# GSM-Arduino-Custom-Board.net
KiCad netlist of a schematic drawn in Altium Designer
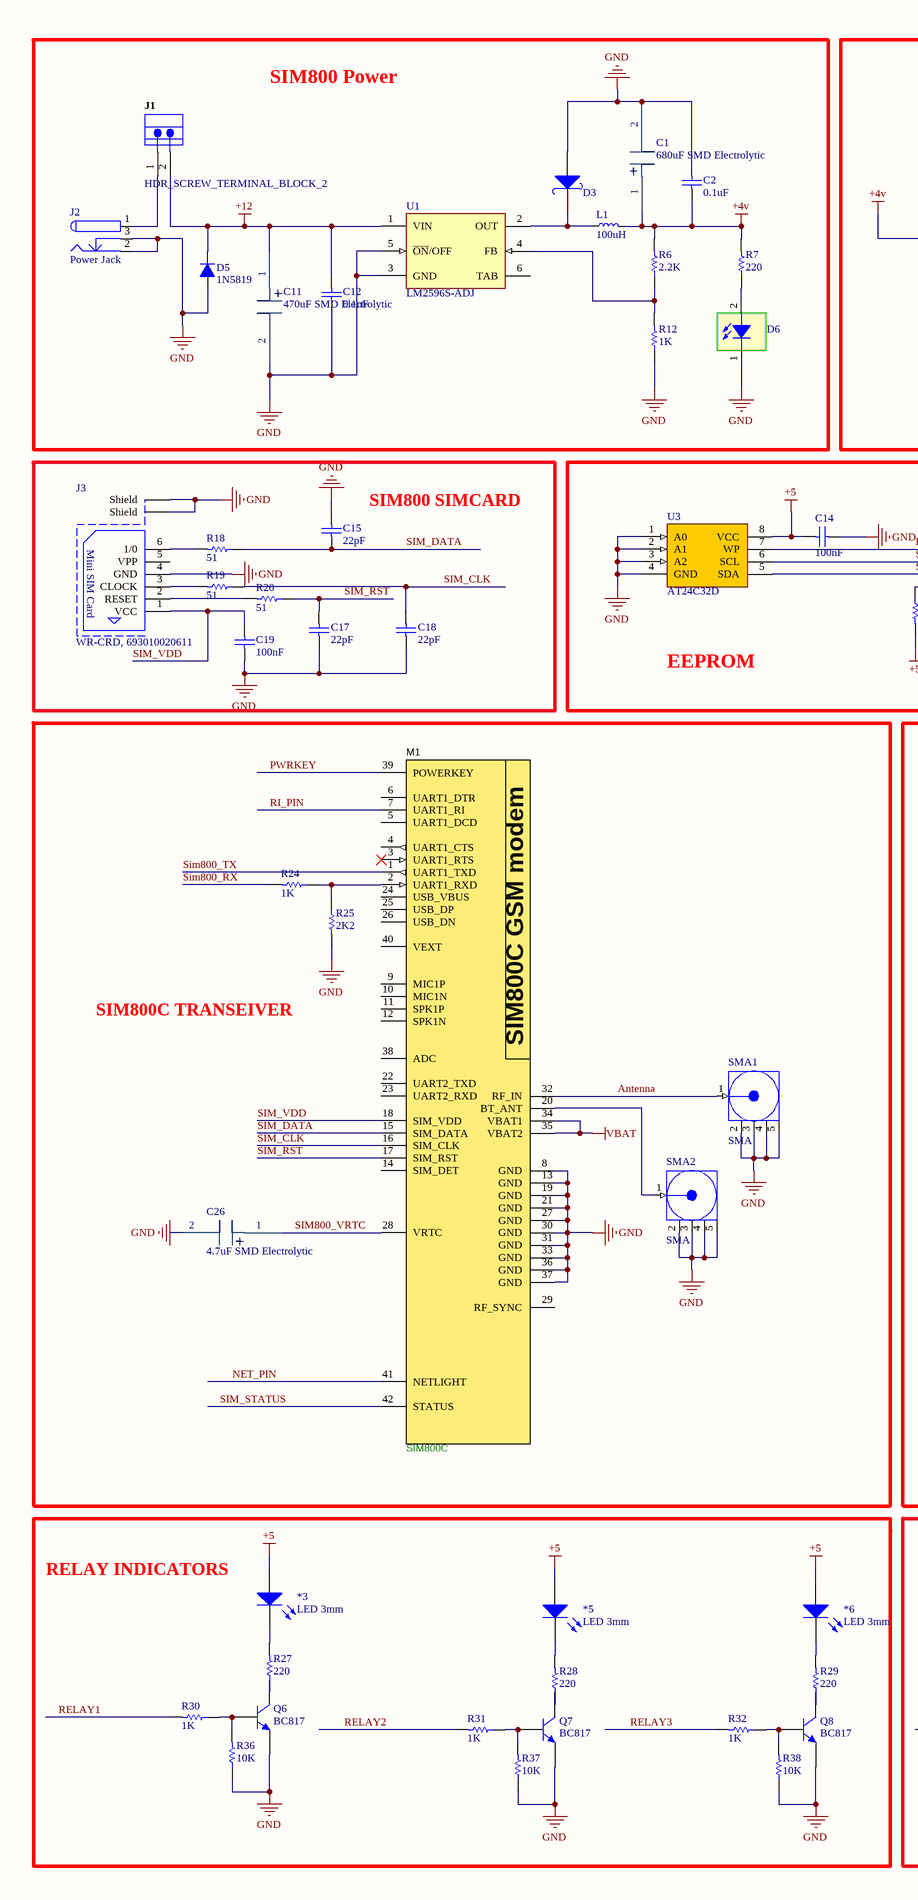
[diagram p0: GSM-Arduino-Custom-Board.SchDoc, left]
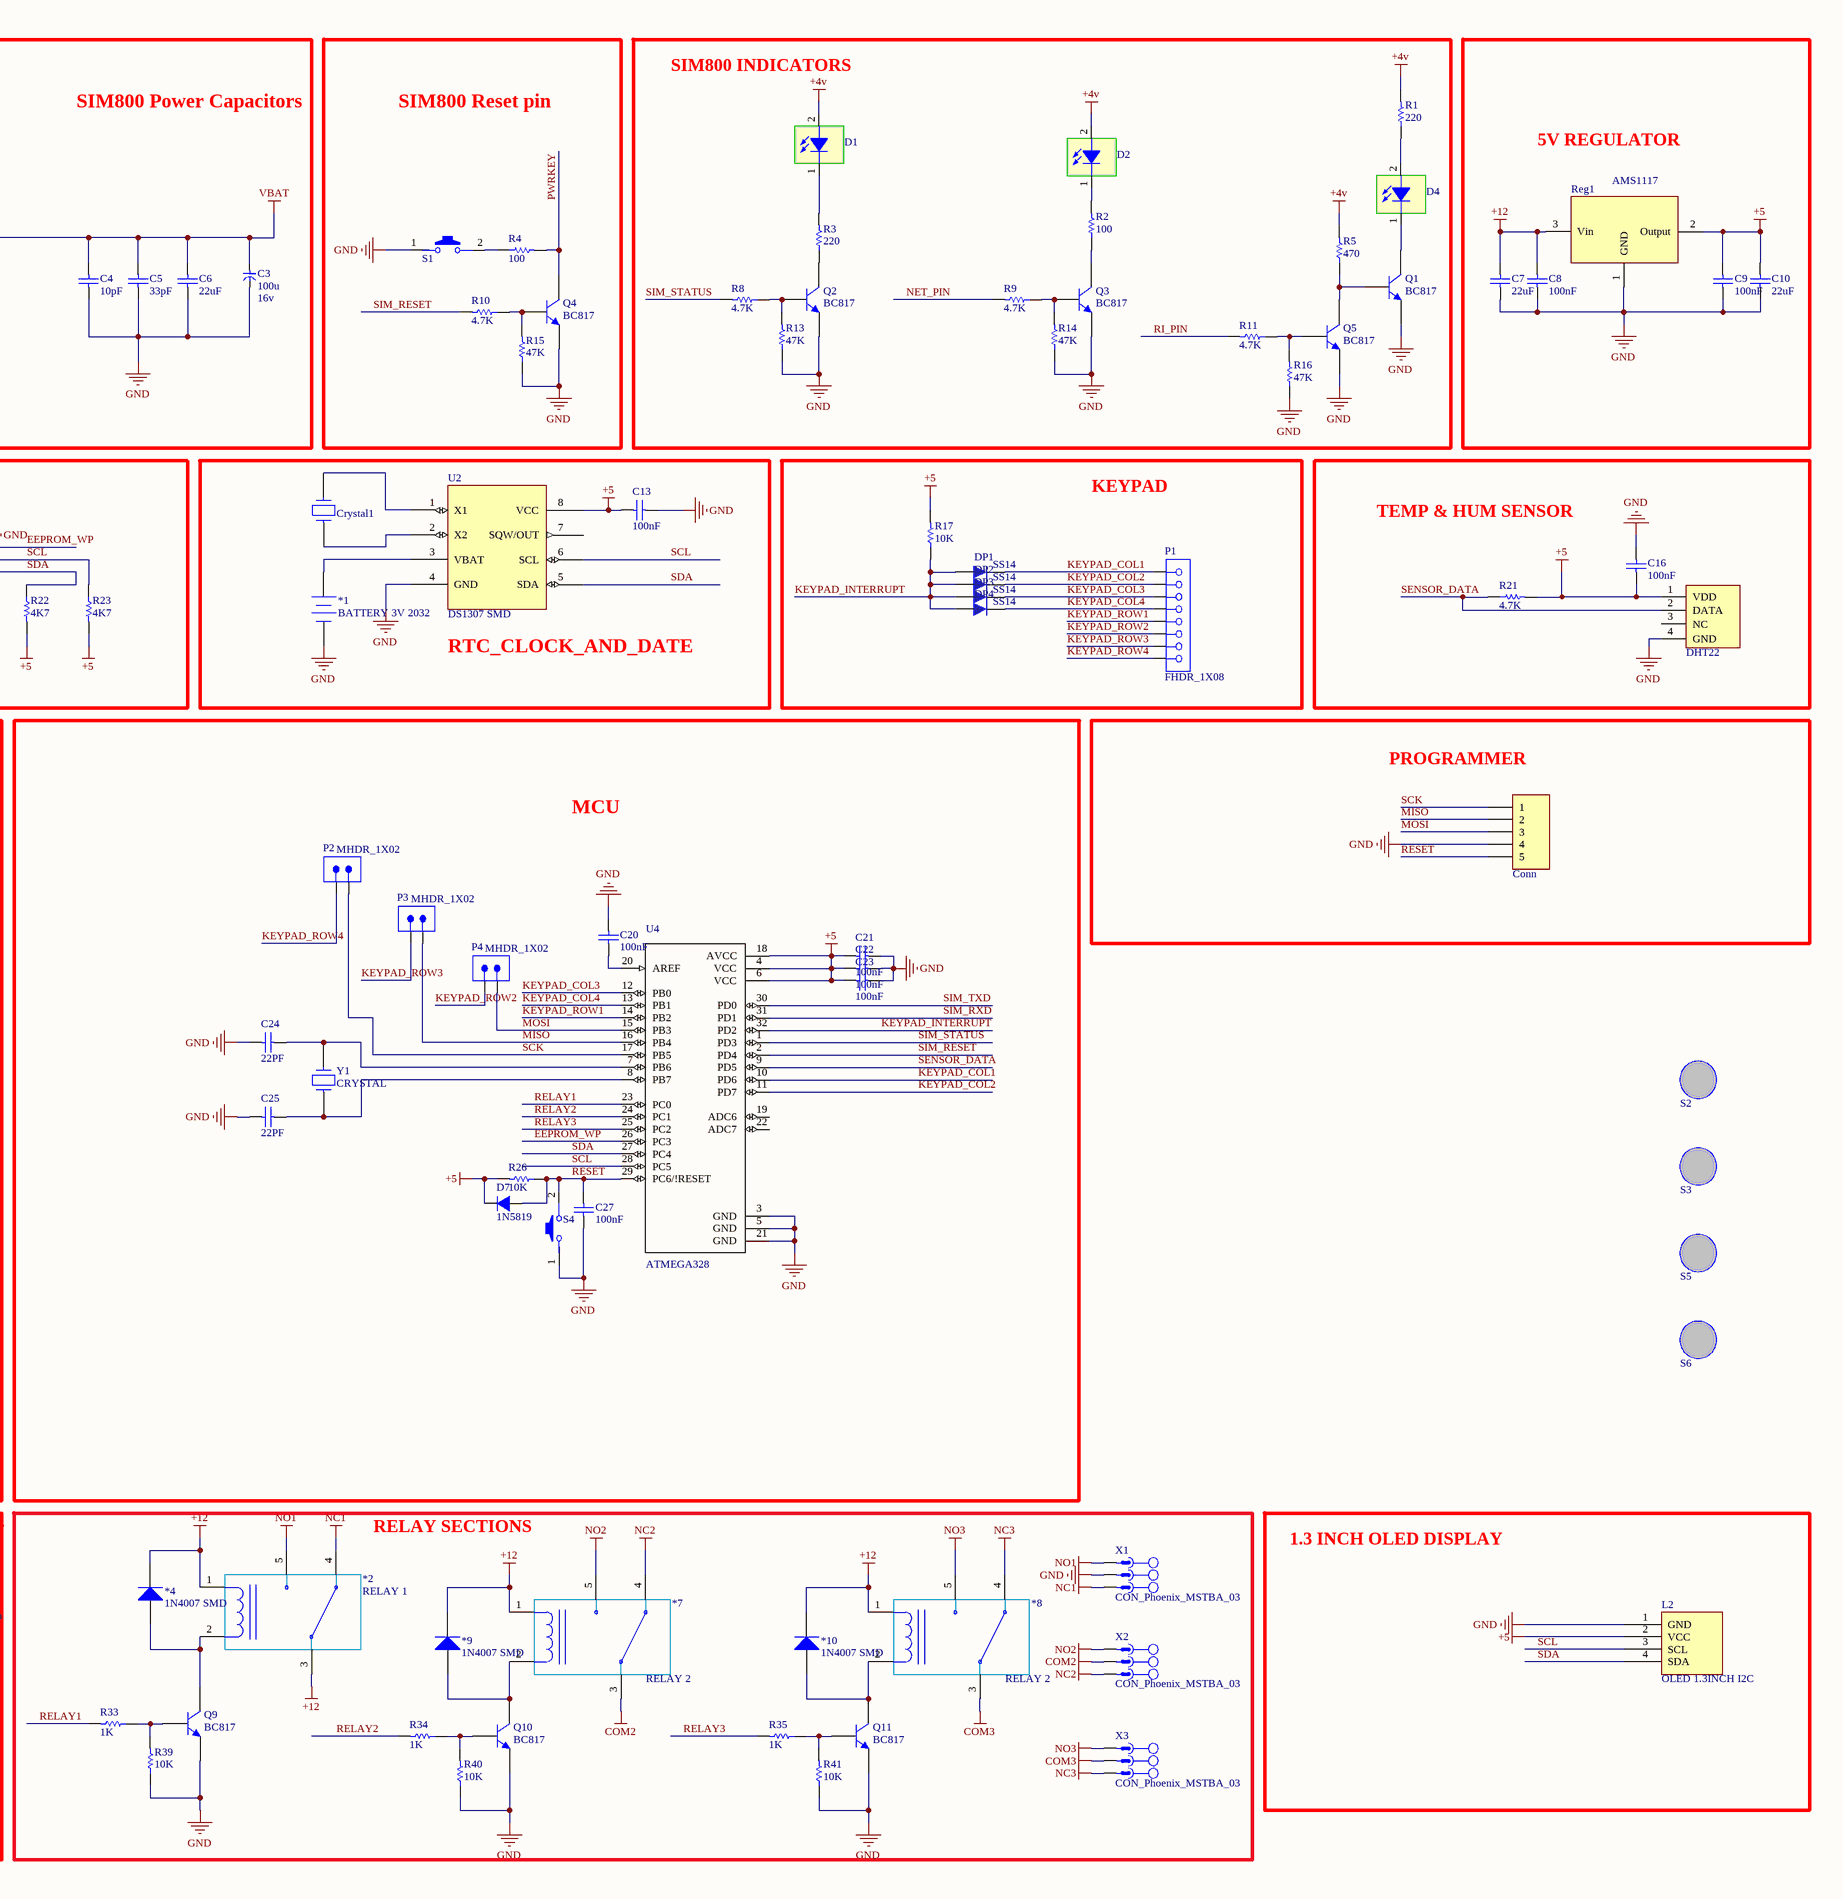
[diagram p1: GSM-Arduino-Custom-Board.SchDoc, right]

(export (version "E")
  (design (tool "Eeschema 10.0.6"))
  (components
    (comp (ref "*1")
      (value "BATTERY 3V 2032")
      (footprint "batt")
      (libsource (lib "General_04") (part "BATTERY 3V 2032"))
    )
    (comp (ref "*2") (value "RELAY 1") (footprint "relay 3") (libsource (lib "General_04") (part "RELAY 1")))
    (comp (ref "*3") (value "LED 3mm") (footprint "led 3mm") (libsource (lib "General_04") (part "LED 3mm")))
    (comp (ref "*4")
      (value "1N4007 SMD")
      (footprint "1N4007 SMD")
      (libsource (lib "General_04") (part "1N4007 SMD"))
    )
    (comp (ref "*5") (value "LED 3mm") (footprint "led 3mm") (libsource (lib "General_04") (part "LED 3mm")))
    (comp (ref "*6") (value "LED 3mm") (footprint "led 3mm") (libsource (lib "General_04") (part "LED 3mm")))
    (comp (ref "*7") (value "RELAY 2") (footprint "relay 3") (libsource (lib "General_04") (part "RELAY 1")))
    (comp (ref "*8") (value "RELAY 2") (footprint "relay 3") (libsource (lib "General_04") (part "RELAY 1")))
    (comp (ref "*9")
      (value "1N4007 SMD")
      (footprint "1N4007 SMD")
      (libsource (lib "General_04") (part "1N4007 SMD"))
    )
    (comp (ref "*10")
      (value "1N4007 SMD")
      (footprint "1N4007 SMD")
      (libsource (lib "General_04") (part "1N4007 SMD"))
    )
    (comp (ref "C1")
      (value "680uF SMD Electrolytic")
      (footprint "SMD Electrolytic Capacitor 8 x 10.2")
      (libsource (lib "RezaKH-Exclusive-LIB") (part "SMD Electrolytic Capacitor 8 x 10.2"))
    )
    (comp (ref "C2")
      (value "0.1uF")
      (footprint "CAPC4817X12N")
      (description "CAP 1206")
      (fields (field (name "DESIGNER") "Abbas Basereh"))
      (libsource (lib "General 1") (part "CAP SMD 1206"))
    )
    (comp (ref "C3")
      (value "100u")
      (footprint "TANTAL CAPACITOR SMD B")
      (description "TANTAL CAPACITOR")
      (fields (field (name "POWER") "16v") (field (name "DESIGNER") "Danial mirzaei"))
      (libsource (lib "My_Lib") (part "TANTAL CAP SMD B"))
    )
    (comp (ref "C4")
      (value "10pF")
      (footprint "CAPC4817X12N")
      (description "CAP 1206")
      (fields (field (name "DESIGNER") "Abbas Basereh"))
      (libsource (lib "General 1") (part "CAP SMD 1206"))
    )
    (comp (ref "C5")
      (value "33pF")
      (footprint "CAPC4817X12N")
      (description "CAP 1206")
      (fields (field (name "DESIGNER") "Abbas Basereh"))
      (libsource (lib "General 1") (part "CAP SMD 1206"))
    )
    (comp (ref "C6")
      (value "22uF")
      (footprint "CAPC4817X12N")
      (description "CAP 1206")
      (fields (field (name "DESIGNER") "Abbas Basereh"))
      (libsource (lib "General 1") (part "CAP SMD 1206"))
    )
    (comp (ref "C7")
      (value "22uF")
      (footprint "CAPC4817X12N")
      (description "CAP 1206")
      (fields (field (name "DESIGNER") "Abbas Basereh"))
      (libsource (lib "General 1") (part "CAP SMD 1206"))
    )
    (comp (ref "C8")
      (value "100nF")
      (footprint "CAPC4817X12N")
      (description "CAP 1206")
      (fields (field (name "DESIGNER") "Abbas Basereh"))
      (libsource (lib "General 1") (part "CAP SMD 1206"))
    )
    (comp (ref "C9")
      (value "100nF")
      (footprint "CAPC4817X12N")
      (description "CAP 1206")
      (fields (field (name "DESIGNER") "Abbas Basereh"))
      (libsource (lib "General 1") (part "CAP SMD 1206"))
    )
    (comp (ref "C10")
      (value "22uF")
      (footprint "CAPC4817X12N")
      (description "CAP 1206")
      (fields (field (name "DESIGNER") "Abbas Basereh"))
      (libsource (lib "General 1") (part "CAP SMD 1206"))
    )
    (comp (ref "C11")
      (value "470uF SMD Electrolytic")
      (footprint "SMD Electrolytic Capacitor 8 x 10.2")
      (libsource (lib "RezaKH-Exclusive-LIB") (part "SMD Electrolytic Capacitor 8 x 10.2"))
    )
    (comp (ref "C12")
      (value "0.1uF")
      (footprint "CAPC4817X12N")
      (description "CAP 1206")
      (fields (field (name "DESIGNER") "Abbas Basereh"))
      (libsource (lib "General 1") (part "CAP SMD 1206"))
    )
    (comp (ref "C13")
      (value "100nF")
      (footprint "CAPC4817X12N")
      (description "CAP 1206")
      (fields (field (name "DESIGNER") "Abbas Basereh"))
      (libsource (lib "General 1") (part "CAP SMD 1206"))
    )
    (comp (ref "C14")
      (value "100nF")
      (footprint "CAPC4817X12N")
      (description "CAP 1206")
      (fields (field (name "DESIGNER") "Abbas Basereh"))
      (libsource (lib "General 1") (part "CAP SMD 1206"))
    )
    (comp (ref "C15")
      (value "22pF")
      (footprint "CAPC4817X12N")
      (description "CAP 1206")
      (fields (field (name "DESIGNER") "Abbas Basereh"))
      (libsource (lib "General 1") (part "CAP SMD 1206"))
    )
    (comp (ref "C16")
      (value "100nF")
      (footprint "CAPC4817X12N")
      (description "CAP 1206")
      (fields (field (name "DESIGNER") "Abbas Basereh"))
      (libsource (lib "General 1") (part "CAP SMD 1206"))
    )
    (comp (ref "C17")
      (value "22pF")
      (footprint "CAPC4817X12N")
      (description "CAP 1206")
      (fields (field (name "DESIGNER") "Abbas Basereh"))
      (libsource (lib "General 1") (part "CAP SMD 1206"))
    )
    (comp (ref "C18")
      (value "22pF")
      (footprint "CAPC4817X12N")
      (description "CAP 1206")
      (fields (field (name "DESIGNER") "Abbas Basereh"))
      (libsource (lib "General 1") (part "CAP SMD 1206"))
    )
    (comp (ref "C19")
      (value "100nF")
      (footprint "CAPC4817X12N")
      (description "CAP 1206")
      (fields (field (name "DESIGNER") "Abbas Basereh"))
      (libsource (lib "General 1") (part "CAP SMD 1206"))
    )
    (comp (ref "C20")
      (value "100nF")
      (footprint "CAPC4817X12N")
      (description "CAP 1206")
      (fields (field (name "DESIGNER") "Abbas Basereh"))
      (libsource (lib "General 1") (part "CAP SMD 1206"))
    )
    (comp (ref "C21")
      (value "100nF")
      (footprint "CAPC4817X12N")
      (description "CAP 1206")
      (fields (field (name "DESIGNER") "Abbas Basereh"))
      (libsource (lib "General 1") (part "CAP SMD 1206"))
    )
    (comp (ref "C22")
      (value "100nF")
      (footprint "CAPC4817X12N")
      (description "CAP 1206")
      (fields (field (name "DESIGNER") "Abbas Basereh"))
      (libsource (lib "General 1") (part "CAP SMD 1206"))
    )
    (comp (ref "C23")
      (value "100nF")
      (footprint "CAPC4817X12N")
      (description "CAP 1206")
      (fields (field (name "DESIGNER") "Abbas Basereh"))
      (libsource (lib "General 1") (part "CAP SMD 1206"))
    )
    (comp (ref "C24")
      (value "22PF")
      (footprint "CAPC4817X12N")
      (description "CAP 1206")
      (fields (field (name "DESIGNER") "Abbas Basereh"))
      (libsource (lib "General 1") (part "CAP SMD 1206"))
    )
    (comp (ref "C25")
      (value "22PF")
      (footprint "CAPC4817X12N")
      (description "CAP 1206")
      (fields (field (name "DESIGNER") "Abbas Basereh"))
      (libsource (lib "General 1") (part "CAP SMD 1206"))
    )
    (comp (ref "C26")
      (value "4.7uF SMD Electrolytic")
      (footprint "SMD Electrolytic Capacitor 4x5.2")
      (libsource (lib "RezaKH-Exclusive-LIB") (part "SMD Electrolytic Capacitor 8 x 10.2"))
    )
    (comp (ref "C27")
      (value "100nF")
      (footprint "CAPC4817X12N")
      (description "CAP 1206")
      (fields (field (name "DESIGNER") "Abbas Basereh"))
      (libsource (lib "General 1") (part "CAP SMD 1206"))
    )
    (comp (ref "Conn")
      (value "Telecommunications")
      (footprint "Teleconn_5pin")
      (fields (field (name "PUBLISHER") "Altium Limited"))
      (libsource (lib "General_10") (part "CON_Telecommunications_5pin"))
    )
    (comp (ref "Crystal1")
      (value "Crystal")
      (footprint "Crystal_2")
      (fields (field (name "PUBLISHER") "Altium Limited"))
      (libsource (lib "General_10") (part "Crystal.."))
    )
    (comp (ref "D1")
      (value "SMD 1206 LED")
      (footprint "LED 1206")
      (libsource (lib "General_14") (part "LED SMD 1206"))
    )
    (comp (ref "D2")
      (value "SMD 1206 LED")
      (footprint "LED 1206")
      (libsource (lib "General_14") (part "LED SMD 1206"))
    )
    (comp (ref "D3")
      (value "1n5822")
      (footprint "DO-214AB(SMC)")
      (description "Schottky Rectifiers")
      (fields
        (field (name "MANUFACTURER") "ON Semiconductor/Fairchild")
        (field (name "DESIGNER") "Abbas Basereh")
      )
      (libsource (lib "General_14") (part "1N5822 SMD"))
    )
    (comp (ref "D4")
      (value "SMD 1206 LED")
      (footprint "LED 1206")
      (libsource (lib "General_14") (part "LED SMD 1206"))
    )
    (comp (ref "D5")
      (value "1N5819")
      (footprint "DO-214AC")
      (description "Schottky diode")
      (libsource (lib "General_09") (part "1N5819"))
    )
    (comp (ref "D6")
      (value "SMD 1206 LED")
      (footprint "LED 1206")
      (libsource (lib "General_14") (part "LED SMD 1206"))
    )
    (comp (ref "D7")
      (value "1N5819")
      (footprint "DO-214AC")
      (description "Schottky diode")
      (libsource (lib "General_09") (part "1N5819"))
    )
    (comp (ref "DHT22")
      (value "DHT22")
      (footprint "DHT22")
      (description "Temprature & Humidity Sensor")
      (libsource (lib "General_12") (part "DHT22"))
    )
    (comp (ref "DP1")
      (value "SS14")
      (footprint "430X270D")
      (description "Schottkey Rectifiers")
      (fields (field (name "DESIGNER") "Abbas Basereh"))
      (libsource (lib "General 1") (part "1N5819"))
    )
    (comp (ref "DP2")
      (value "SS14")
      (footprint "430X270D")
      (description "Schottkey Rectifiers")
      (fields (field (name "DESIGNER") "Abbas Basereh"))
      (libsource (lib "General 1") (part "1N5819"))
    )
    (comp (ref "DP3")
      (value "SS14")
      (footprint "430X270D")
      (description "Schottkey Rectifiers")
      (fields (field (name "DESIGNER") "Abbas Basereh"))
      (libsource (lib "General 1") (part "1N5819"))
    )
    (comp (ref "DP4")
      (value "SS14")
      (footprint "430X270D")
      (description "Schottkey Rectifiers")
      (fields (field (name "DESIGNER") "Abbas Basereh"))
      (libsource (lib "General 1") (part "1N5819"))
    )
    (comp (ref "J1")
      (value "HDR_SCREW_TERMINAL_BLOCK_2")
      (footprint "Socket Blue 2")
      (fields (field (name "DESIGNER") "Eng. Saeid Jorablo") (field (name "PUBLISHER") "SJ UnLimited"))
      (libsource (lib "Sockets And Connectors") (part "HDR_SCREW_TERMINAL_BLOCK_2"))
    )
    (comp (ref "J2")
      (value "Power Jack")
      (footprint "Power Jack")
      (fields (field (name "DESIGNER") "Saeid Jorablo"))
      (libsource (lib "RezaKH-Exclusive-LIB") (part "Power Jack"))
    )
    (comp (ref "J3")
      (value "WR-CRD, 693010020611")
      (footprint "693010020611")
      (description "WR-CRD Mini SIM")
      (fields
        (field (name "MANUFACTURER") "Würth Elektronik eiSos GmbH")
        (field (name "PARTNO") "693010020611")
        (field (name "CREATED BY") "Karrer Zheng")
      )
      (libsource (lib "Connector_16 WE_WR-CRD_Card Connectors_rev16a") (part "WR-CRD, 693010020611"))
    )
    (comp (ref "L1")
      (value "100uH")
      (footprint "inductor smd")
      (description "Made By Danial Mirzaei")
      (libsource (lib "My_Lib") (part "inductor smd"))
    )
    (comp (ref "L2")
      (value "OLED 1.3INCH I2C")
      (footprint "OLED 1.3INCH I2C")
      (libsource (lib "RezaKH-Exclusive-LIB") (part "OLED 1.3 INCH LCD I2C"))
    )
    (comp (ref "M1") (value "SIM800C") (footprint "SIM800C") (libsource (lib "sim800") (part "SIM800C")))
    (comp (ref "P1")
      (value "FHDR_1X08")
      (footprint "FHDR1X08-254P")
      (description "Female Header 1X08")
      (libsource (lib "Connector_15 and Sockets") (part "FHDR_1X08"))
    )
    (comp (ref "P2")
      (value "MHDR_1X02")
      (footprint "MHDR1X02-254P")
      (description "Male Header 1X02")
      (libsource (lib "Connector_15 and Sockets") (part "MHDR_1X02"))
    )
    (comp (ref "P3")
      (value "MHDR_1X02")
      (footprint "MHDR1X02-254P")
      (description "Male Header 1X02")
      (libsource (lib "Connector_15 and Sockets") (part "MHDR_1X02"))
    )
    (comp (ref "P4")
      (value "MHDR_1X02")
      (footprint "MHDR1X02-254P")
      (description "Male Header 1X02")
      (libsource (lib "Connector_15 and Sockets") (part "MHDR_1X02"))
    )
    (comp (ref "Q1")
      (value "BC817")
      (footprint "SOT23_N")
      (description "45 V, 500 mA NPN general-purpose transistors")
      (fields (field (name "PUBLISHER") "Abbas Basereh"))
      (libsource (lib "General_11") (part "BC817"))
    )
    (comp (ref "Q2")
      (value "BC817")
      (footprint "SOT23_N")
      (description "45 V, 500 mA NPN general-purpose transistors")
      (fields (field (name "PUBLISHER") "Abbas Basereh"))
      (libsource (lib "General_11") (part "BC817"))
    )
    (comp (ref "Q3")
      (value "BC817")
      (footprint "SOT23_N")
      (description "45 V, 500 mA NPN general-purpose transistors")
      (fields (field (name "PUBLISHER") "Abbas Basereh"))
      (libsource (lib "General_11") (part "BC817"))
    )
    (comp (ref "Q4")
      (value "BC817")
      (footprint "SOT23_N")
      (description "45 V, 500 mA NPN general-purpose transistors")
      (fields (field (name "PUBLISHER") "Abbas Basereh"))
      (libsource (lib "General_11") (part "BC817"))
    )
    (comp (ref "Q5")
      (value "BC817")
      (footprint "SOT23_N")
      (description "45 V, 500 mA NPN general-purpose transistors")
      (fields (field (name "PUBLISHER") "Abbas Basereh"))
      (libsource (lib "General_11") (part "BC817"))
    )
    (comp (ref "Q6")
      (value "BC817")
      (footprint "SOT23_N")
      (description "45 V, 500 mA NPN general-purpose transistors")
      (fields (field (name "PUBLISHER") "Abbas Basereh"))
      (libsource (lib "General_11") (part "BC817"))
    )
    (comp (ref "Q7")
      (value "BC817")
      (footprint "SOT23_N")
      (description "45 V, 500 mA NPN general-purpose transistors")
      (fields (field (name "PUBLISHER") "Abbas Basereh"))
      (libsource (lib "General_11") (part "BC817"))
    )
    (comp (ref "Q8")
      (value "BC817")
      (footprint "SOT23_N")
      (description "45 V, 500 mA NPN general-purpose transistors")
      (fields (field (name "PUBLISHER") "Abbas Basereh"))
      (libsource (lib "General_11") (part "BC817"))
    )
    (comp (ref "Q9")
      (value "BC817")
      (footprint "SOT23_N")
      (description "45 V, 500 mA NPN general-purpose transistors")
      (fields (field (name "PUBLISHER") "Abbas Basereh"))
      (libsource (lib "General_11") (part "BC817"))
    )
    (comp (ref "Q10")
      (value "BC817")
      (footprint "SOT23_N")
      (description "45 V, 500 mA NPN general-purpose transistors")
      (fields (field (name "PUBLISHER") "Abbas Basereh"))
      (libsource (lib "General_11") (part "BC817"))
    )
    (comp (ref "Q11")
      (value "BC817")
      (footprint "SOT23_N")
      (description "45 V, 500 mA NPN general-purpose transistors")
      (fields (field (name "PUBLISHER") "Abbas Basereh"))
      (libsource (lib "General_11") (part "BC817"))
    )
    (comp (ref "R1")
      (value "220")
      (footprint "RESC4817X04N")
      (description "RES 1206")
      (fields (field (name "DESIGNER") "Abbas Basereh"))
      (libsource (lib "General 1") (part "RES 1206 0.25W"))
    )
    (comp (ref "R2")
      (value "100")
      (footprint "RESC4817X04N")
      (description "RES 1206")
      (fields (field (name "DESIGNER") "Abbas Basereh"))
      (libsource (lib "General 1") (part "RES 1206 0.25W"))
    )
    (comp (ref "R3")
      (value "220")
      (footprint "RESC4817X04N")
      (description "RES 1206")
      (fields (field (name "DESIGNER") "Abbas Basereh"))
      (libsource (lib "General 1") (part "RES 1206 0.25W"))
    )
    (comp (ref "R4")
      (value "100")
      (footprint "RESC4817X04N")
      (description "RES 1206")
      (fields (field (name "DESIGNER") "Abbas Basereh"))
      (libsource (lib "General 1") (part "RES 1206 0.25W"))
    )
    (comp (ref "R5")
      (value "470")
      (footprint "RESC4817X04N")
      (description "RES 1206")
      (fields (field (name "DESIGNER") "Abbas Basereh"))
      (libsource (lib "General 1") (part "RES 1206 0.25W"))
    )
    (comp (ref "R6")
      (value "2.2K")
      (footprint "RESC4817X04N")
      (description "RES 1206")
      (fields (field (name "DESIGNER") "Abbas Basereh"))
      (libsource (lib "General 1") (part "RES 1206 0.25W"))
    )
    (comp (ref "R7")
      (value "220")
      (footprint "RESC4817X04N")
      (description "RES 1206")
      (fields (field (name "DESIGNER") "Abbas Basereh"))
      (libsource (lib "General 1") (part "RES 1206 0.25W"))
    )
    (comp (ref "R8")
      (value "4.7K")
      (footprint "RESC4817X04N")
      (description "RES 1206")
      (fields (field (name "DESIGNER") "Abbas Basereh"))
      (libsource (lib "General 1") (part "RES 1206 0.25W"))
    )
    (comp (ref "R9")
      (value "4.7K")
      (footprint "RESC4817X04N")
      (description "RES 1206")
      (fields (field (name "DESIGNER") "Abbas Basereh"))
      (libsource (lib "General 1") (part "RES 1206 0.25W"))
    )
    (comp (ref "R10")
      (value "4.7K")
      (footprint "RESC4817X04N")
      (description "RES 1206")
      (fields (field (name "DESIGNER") "Abbas Basereh"))
      (libsource (lib "General 1") (part "RES 1206 0.25W"))
    )
    (comp (ref "R11")
      (value "4.7K")
      (footprint "RESC4817X04N")
      (description "RES 1206")
      (fields (field (name "DESIGNER") "Abbas Basereh"))
      (libsource (lib "General 1") (part "RES 1206 0.25W"))
    )
    (comp (ref "R12")
      (value "1K")
      (footprint "RESC4817X04N")
      (description "RES 1206")
      (fields (field (name "DESIGNER") "Abbas Basereh"))
      (libsource (lib "General 1") (part "RES 1206 0.25W"))
    )
    (comp (ref "R13")
      (value "47K")
      (footprint "RESC4817X04N")
      (description "RES 1206")
      (fields (field (name "DESIGNER") "Abbas Basereh"))
      (libsource (lib "General 1") (part "RES 1206 0.25W"))
    )
    (comp (ref "R14")
      (value "47K")
      (footprint "RESC4817X04N")
      (description "RES 1206")
      (fields (field (name "DESIGNER") "Abbas Basereh"))
      (libsource (lib "General 1") (part "RES 1206 0.25W"))
    )
    (comp (ref "R15")
      (value "47K")
      (footprint "RESC4817X04N")
      (description "RES 1206")
      (fields (field (name "DESIGNER") "Abbas Basereh"))
      (libsource (lib "General 1") (part "RES 1206 0.25W"))
    )
    (comp (ref "R16")
      (value "47K")
      (footprint "RESC4817X04N")
      (description "RES 1206")
      (fields (field (name "DESIGNER") "Abbas Basereh"))
      (libsource (lib "General 1") (part "RES 1206 0.25W"))
    )
    (comp (ref "R17")
      (value "10K")
      (footprint "RESC4817X04N")
      (description "RES 1206")
      (fields (field (name "DESIGNER") "Abbas Basereh"))
      (libsource (lib "General 1") (part "RES 1206 0.25W"))
    )
    (comp (ref "R18")
      (value "51")
      (footprint "RESC4817X04N")
      (description "RES 1206")
      (fields (field (name "DESIGNER") "Abbas Basereh"))
      (libsource (lib "General 1") (part "RES 1206 0.25W"))
    )
    (comp (ref "R19")
      (value "51")
      (footprint "RESC4817X04N")
      (description "RES 1206")
      (fields (field (name "DESIGNER") "Abbas Basereh"))
      (libsource (lib "General 1") (part "RES 1206 0.25W"))
    )
    (comp (ref "R20")
      (value "51")
      (footprint "RESC4817X04N")
      (description "RES 1206")
      (fields (field (name "DESIGNER") "Abbas Basereh"))
      (libsource (lib "General 1") (part "RES 1206 0.25W"))
    )
    (comp (ref "R21")
      (value "4.7K")
      (footprint "RESC4817X04N")
      (description "RES 1206")
      (fields (field (name "DESIGNER") "Abbas Basereh"))
      (libsource (lib "General 1") (part "RES 1206 0.25W"))
    )
    (comp (ref "R22")
      (value "4K7")
      (footprint "RESC4817X04N")
      (description "RES 1206")
      (fields (field (name "DESIGNER") "Abbas Basereh"))
      (libsource (lib "General 1") (part "RES 1206 0.25W"))
    )
    (comp (ref "R23")
      (value "4K7")
      (footprint "RESC4817X04N")
      (description "RES 1206")
      (fields (field (name "DESIGNER") "Abbas Basereh"))
      (libsource (lib "General 1") (part "RES 1206 0.25W"))
    )
    (comp (ref "R24")
      (value "1K")
      (footprint "RESC4817X04N")
      (description "RES 1206")
      (fields (field (name "DESIGNER") "Abbas Basereh"))
      (libsource (lib "General 1") (part "RES 1206 0.25W"))
    )
    (comp (ref "R25")
      (value "2K2")
      (footprint "RESC4817X04N")
      (description "RES 1206")
      (fields (field (name "DESIGNER") "Abbas Basereh"))
      (libsource (lib "General 1") (part "RES 1206 0.25W"))
    )
    (comp (ref "R26")
      (value "10K")
      (footprint "RESC4817X04N")
      (description "RES 1206")
      (fields (field (name "DESIGNER") "Abbas Basereh"))
      (libsource (lib "General 1") (part "RES 1206 0.25W"))
    )
    (comp (ref "R27")
      (value "220")
      (footprint "RESC4817X04N")
      (description "RES 1206")
      (fields (field (name "DESIGNER") "Abbas Basereh"))
      (libsource (lib "General 1") (part "RES 1206 0.25W"))
    )
    (comp (ref "R28")
      (value "220")
      (footprint "RESC4817X04N")
      (description "RES 1206")
      (fields (field (name "DESIGNER") "Abbas Basereh"))
      (libsource (lib "General 1") (part "RES 1206 0.25W"))
    )
    (comp (ref "R29")
      (value "220")
      (footprint "RESC4817X04N")
      (description "RES 1206")
      (fields (field (name "DESIGNER") "Abbas Basereh"))
      (libsource (lib "General 1") (part "RES 1206 0.25W"))
    )
    (comp (ref "R30")
      (value "1K")
      (footprint "RESC4817X04N")
      (description "RES 1206")
      (fields (field (name "DESIGNER") "Abbas Basereh"))
      (libsource (lib "General 1") (part "RES 1206 0.25W"))
    )
    (comp (ref "R31")
      (value "1K")
      (footprint "RESC4817X04N")
      (description "RES 1206")
      (fields (field (name "DESIGNER") "Abbas Basereh"))
      (libsource (lib "General 1") (part "RES 1206 0.25W"))
    )
    (comp (ref "R32")
      (value "1K")
      (footprint "RESC4817X04N")
      (description "RES 1206")
      (fields (field (name "DESIGNER") "Abbas Basereh"))
      (libsource (lib "General 1") (part "RES 1206 0.25W"))
    )
    (comp (ref "R33")
      (value "1K")
      (footprint "RESC4817X04N")
      (description "RES 1206")
      (fields (field (name "DESIGNER") "Abbas Basereh"))
      (libsource (lib "General 1") (part "RES 1206 0.25W"))
    )
    (comp (ref "R34")
      (value "1K")
      (footprint "RESC4817X04N")
      (description "RES 1206")
      (fields (field (name "DESIGNER") "Abbas Basereh"))
      (libsource (lib "General 1") (part "RES 1206 0.25W"))
    )
    (comp (ref "R35")
      (value "1K")
      (footprint "RESC4817X04N")
      (description "RES 1206")
      (fields (field (name "DESIGNER") "Abbas Basereh"))
      (libsource (lib "General 1") (part "RES 1206 0.25W"))
    )
    (comp (ref "R36")
      (value "10K")
      (footprint "RESC4817X04N")
      (description "RES 1206")
      (fields (field (name "DESIGNER") "Abbas Basereh"))
      (libsource (lib "General 1") (part "RES 1206 0.25W"))
    )
    (comp (ref "R37")
      (value "10K")
      (footprint "RESC4817X04N")
      (description "RES 1206")
      (fields (field (name "DESIGNER") "Abbas Basereh"))
      (libsource (lib "General 1") (part "RES 1206 0.25W"))
    )
    (comp (ref "R38")
      (value "10K")
      (footprint "RESC4817X04N")
      (description "RES 1206")
      (fields (field (name "DESIGNER") "Abbas Basereh"))
      (libsource (lib "General 1") (part "RES 1206 0.25W"))
    )
    (comp (ref "R39")
      (value "10K")
      (footprint "RESC4817X04N")
      (description "RES 1206")
      (fields (field (name "DESIGNER") "Abbas Basereh"))
      (libsource (lib "General 1") (part "RES 1206 0.25W"))
    )
    (comp (ref "R40")
      (value "10K")
      (footprint "RESC4817X04N")
      (description "RES 1206")
      (fields (field (name "DESIGNER") "Abbas Basereh"))
      (libsource (lib "General 1") (part "RES 1206 0.25W"))
    )
    (comp (ref "R41")
      (value "10K")
      (footprint "RESC4817X04N")
      (description "RES 1206")
      (fields (field (name "DESIGNER") "Abbas Basereh"))
      (libsource (lib "General 1") (part "RES 1206 0.25W"))
    )
    (comp (ref "Reg1")
      (value "AMS1117")
      (footprint "AMS1117 3.3")
      (libsource (lib "General_04") (part "AMS1117"))
    )
    (comp (ref "S1")
      (value "SW_PB2")
      (footprint "SMD_ALPS_SKQMBBE010")
      (description "2 Pin Push Button Switch")
      (fields (field (name "DESIGNER") "Eng. Saeid Jorablo"))
      (libsource (lib "Switches") (part "SW_PB2"))
    )
    (comp (ref "S2")
      (value "Screw")
      (footprint "MY_PAD_3MM")
      (description "3mm Screw")
      (libsource (lib "General_31") (part "Screw"))
    )
    (comp (ref "S3")
      (value "Screw")
      (footprint "MY_PAD_3MM")
      (description "3mm Screw")
      (libsource (lib "General_31") (part "Screw"))
    )
    (comp (ref "S4")
      (value "SW_PB2")
      (footprint "SMD_ALPS_SKQMBBE010")
      (description "2 Pin Push Button Switch")
      (fields (field (name "DESIGNER") "Eng. Saeid Jorablo"))
      (libsource (lib "Switches") (part "SW_PB2"))
    )
    (comp (ref "S5")
      (value "Screw")
      (footprint "MY_PAD_3MM")
      (description "3mm Screw")
      (libsource (lib "General_31") (part "Screw"))
    )
    (comp (ref "S6")
      (value "Screw")
      (footprint "MY_PAD_3MM")
      (description "3mm Screw")
      (libsource (lib "General_31") (part "Screw"))
    )
    (comp (ref "SMA1") (value "SMA") (footprint "SMA ANT") (libsource (lib "General_04") (part "SMA")))
    (comp (ref "SMA2") (value "SMA") (footprint "SMA ANT") (libsource (lib "General_04") (part "SMA")))
    (comp (ref "U1")
      (value "LM2596S-ADJ")
      (footprint "TS5B_N")
      (description "SIMPLE SWITCHER Power Converter 150 KHz 3A Step-Down Voltage Regulator")
      (fields
        (field (name "MANUFACTURER") "National Semiconductor")
        (field (name "DIGIKEYPARTNUMBER") "LM2596S-ADJ-ND")
        (field (name "PUBLISHER") "Altium Limited")
      )
      (libsource (lib "General_07") (part "LM2596S-ADJ"))
    )
    (comp (ref "U2")
      (value "DS1307 SMD")
      (footprint "DS1307 SMD - SO-8")
      (description "DS1307 SMD SO-8 By Reza.K.H")
      (libsource (lib "RezaKH-Exclusive-LIB") (part "DS1307 SMD"))
    )
    (comp (ref "U3")
      (value "AT24C32D")
      (footprint "SO8")
      (description "2-Wire Serial  Electrically  Erasable and  Programmable  Read-only  Memory")
      (libsource (lib "Sajad_Altium_Library") (part "AT24C32D"))
    )
    (comp (ref "U4")
      (value "ATMEGA328")
      (footprint "QFP80P900X900X120-32N")
      (description "MCU 8-bit ATmega AVR RISC 32KB Flash 2.5V/3.3V/5V 32-Pin TQFP Tray")
      (fields (field (name "MF") "Microchip") (field (name "MP") "ATMEGA328P-AN"))
      (libsource (lib "My_Lib") (part "ATMEGA328-smd"))
    )
    (comp (ref "X1")
      (value "CON_Phoenix_MSTBA_03")
      (footprint "CON_MSTBA03")
      (fields
        (field (name "MANUFACTURER") "PHOENIX CONTACT")
        (field (name "VOLTAGE") "320 V")
        (field (name "DESIGNER") "Eng. Saeid Jorablo")
        (field (name "PUBLISHER") "SJ UnLimited")
      )
      (libsource (lib "Connector_15 and Sockets") (part "CON_Phoenix_MSTBA_03"))
    )
    (comp (ref "X2")
      (value "CON_Phoenix_MSTBA_03")
      (footprint "CON_MSTBA03")
      (fields
        (field (name "MANUFACTURER") "PHOENIX CONTACT")
        (field (name "VOLTAGE") "320 V")
        (field (name "DESIGNER") "Eng. Saeid Jorablo")
        (field (name "PUBLISHER") "SJ UnLimited")
      )
      (libsource (lib "Connector_15 and Sockets") (part "CON_Phoenix_MSTBA_03"))
    )
    (comp (ref "X3")
      (value "CON_Phoenix_MSTBA_03")
      (footprint "CON_MSTBA03")
      (fields
        (field (name "MANUFACTURER") "PHOENIX CONTACT")
        (field (name "VOLTAGE") "320 V")
        (field (name "DESIGNER") "Eng. Saeid Jorablo")
        (field (name "PUBLISHER") "SJ UnLimited")
      )
      (libsource (lib "Connector_15 and Sockets") (part "CON_Phoenix_MSTBA_03"))
    )
    (comp (ref "Y1")
      (value "CRYSTAL")
      (footprint "My_Crystal_SMD")
      (description "Crystal")
      (fields (field (name "ASID PART NUMBER") "Crystal-AS"))
      (libsource (lib "Mylib Rev 4") (part "CRYSTAL"))
    )
  )
  (nets
    (net (code "1") (name "+4v") (class "Default")
      (node (ref "C1") (pin "1") (pintype "passive"))
      (node (ref "C2") (pin "1") (pinfunction "1_1") (pintype "passive"))
      (node (ref "C3") (pin "1") (pinfunction "1_1") (pintype "passive"))
      (node (ref "C4") (pin "2") (pinfunction "2_2") (pintype "passive"))
      (node (ref "C5") (pin "2") (pinfunction "2_2") (pintype "passive"))
      (node (ref "C6") (pin "2") (pinfunction "2_2") (pintype "passive"))
      (node (ref "D1") (pin "2") (pinfunction "2_2") (pintype "passive"))
      (node (ref "D2") (pin "2") (pinfunction "2_2") (pintype "passive"))
      (node (ref "L1") (pin "2") (pinfunction "2_2") (pintype "passive"))
      (node (ref "M1") (pin "34") (pinfunction "VBAT1_34") (pintype "passive"))
      (node (ref "M1") (pin "35") (pinfunction "VBAT2_35") (pintype "passive"))
      (node (ref "R1") (pin "2") (pinfunction "2_2") (pintype "passive"))
      (node (ref "R5") (pin "2") (pinfunction "2_2") (pintype "passive"))
      (node (ref "R6") (pin "2") (pinfunction "2_2") (pintype "passive"))
      (node (ref "R7") (pin "2") (pinfunction "2_2") (pintype "passive"))
    )
    (net (code "2") (name "+5") (class "Default")
      (node (ref "*3") (pin "1") (pinfunction "A_1") (pintype "passive"))
      (node (ref "*5") (pin "1") (pinfunction "A_1") (pintype "passive"))
      (node (ref "*6") (pin "1") (pinfunction "A_1") (pintype "passive"))
      (node (ref "C10") (pin "2") (pinfunction "2_2") (pintype "passive"))
      (node (ref "C13") (pin "2") (pinfunction "2_2") (pintype "passive"))
      (node (ref "C14") (pin "2") (pinfunction "2_2") (pintype "passive"))
      (node (ref "C16") (pin "1") (pinfunction "1_1") (pintype "passive"))
      (node (ref "C21") (pin "2") (pinfunction "2_2") (pintype "passive"))
      (node (ref "C22") (pin "2") (pinfunction "2_2") (pintype "passive"))
      (node (ref "C23") (pin "2") (pinfunction "2_2") (pintype "passive"))
      (node (ref "C9") (pin "2") (pinfunction "2_2") (pintype "passive"))
      (node (ref "D7") (pin "1") (pinfunction "1_1") (pintype "passive"))
      (node (ref "DHT22") (pin "1") (pinfunction "VDD_1") (pintype "passive"))
      (node (ref "L2") (pin "2") (pinfunction "VCC_2") (pintype "passive"))
      (node (ref "R17") (pin "2") (pinfunction "2_2") (pintype "passive"))
      (node (ref "R21") (pin "2") (pinfunction "2_2") (pintype "passive"))
      (node (ref "R22") (pin "2") (pinfunction "2_2") (pintype "passive"))
      (node (ref "R23") (pin "2") (pinfunction "2_2") (pintype "passive"))
      (node (ref "R26") (pin "2") (pinfunction "2_2") (pintype "passive"))
      (node (ref "Reg1") (pin "2") (pinfunction "Output_2") (pintype "passive"))
      (node (ref "U2") (pin "8") (pinfunction "VCC_8") (pintype "power_in"))
      (node (ref "U3") (pin "8") (pinfunction "VCC_8") (pintype "power_in"))
      (node (ref "U4") (pin "18") (pinfunction "AVCC_18") (pintype "power_in"))
      (node (ref "U4") (pin "4") (pinfunction "VCC_4") (pintype "power_in"))
      (node (ref "U4") (pin "6") (pinfunction "VCC_6") (pintype "power_in"))
    )
    (net (code "3") (name "+12") (class "Default")
      (node (ref "*10") (pin "2") (pinfunction "K_2") (pintype "passive"))
      (node (ref "*2") (pin "1") (pinfunction "1_1") (pintype "passive"))
      (node (ref "*2") (pin "3") (pinfunction "3_3") (pintype "passive"))
      (node (ref "*4") (pin "2") (pinfunction "K_2") (pintype "passive"))
      (node (ref "*7") (pin "1") (pinfunction "1_1") (pintype "passive"))
      (node (ref "*8") (pin "1") (pinfunction "1_1") (pintype "passive"))
      (node (ref "*9") (pin "2") (pinfunction "K_2") (pintype "passive"))
      (node (ref "C11") (pin "1") (pintype "passive"))
      (node (ref "C12") (pin "2") (pinfunction "2_2") (pintype "passive"))
      (node (ref "C7") (pin "2") (pinfunction "2_2") (pintype "passive"))
      (node (ref "C8") (pin "2") (pinfunction "2_2") (pintype "passive"))
      (node (ref "D5") (pin "1") (pinfunction "1_1") (pintype "passive"))
      (node (ref "J1") (pin "2") (pinfunction "2_2") (pintype "passive"))
      (node (ref "Reg1") (pin "3") (pinfunction "Vin_3") (pintype "passive"))
      (node (ref "U1") (pin "1") (pinfunction "VIN_1") (pintype "power_in"))
    )
    (net (code "4") (name "/Antenna") (class "Default")
      (node (ref "M1") (pin "32") (pinfunction "RF_IN_32") (pintype "passive"))
      (node (ref "SMA1") (pin "1") (pinfunction "Signal_1") (pintype "input"))
    )
    (net (code "5") (name "/EEPROM_WP") (class "Default")
      (node (ref "U3") (pin "7") (pinfunction "WP_7") (pintype "power_in"))
      (node (ref "U4") (pin "26") (pinfunction "PC3_26") (pintype "bidirectional"))
    )
    (net (code "6") (name "/KEYPAD_COL1") (class "Default")
      (node (ref "DP1") (pin "2") (pintype "passive"))
      (node (ref "P1") (pin "1") (pinfunction "1_1") (pintype "passive"))
      (node (ref "U4") (pin "10") (pinfunction "PD6_10") (pintype "bidirectional"))
    )
    (net (code "7") (name "/KEYPAD_COL2") (class "Default")
      (node (ref "DP2") (pin "2") (pintype "passive"))
      (node (ref "P1") (pin "2") (pinfunction "2_2") (pintype "passive"))
      (node (ref "U4") (pin "11") (pinfunction "PD7_11") (pintype "bidirectional"))
    )
    (net (code "8") (name "/KEYPAD_COL3") (class "Default")
      (node (ref "DP3") (pin "2") (pintype "passive"))
      (node (ref "P1") (pin "3") (pinfunction "3_3") (pintype "passive"))
      (node (ref "U4") (pin "12") (pinfunction "PB0_12") (pintype "bidirectional"))
    )
    (net (code "9") (name "/KEYPAD_COL4") (class "Default")
      (node (ref "DP4") (pin "2") (pintype "passive"))
      (node (ref "P1") (pin "4") (pinfunction "4_4") (pintype "passive"))
      (node (ref "U4") (pin "13") (pinfunction "PB1_13") (pintype "bidirectional"))
    )
    (net (code "10") (name "/KEYPAD_INTERRUPT") (class "Default")
      (node (ref "DP1") (pin "1") (pintype "passive"))
      (node (ref "DP2") (pin "1") (pintype "passive"))
      (node (ref "DP3") (pin "1") (pintype "passive"))
      (node (ref "DP4") (pin "1") (pintype "passive"))
      (node (ref "R17") (pin "1") (pinfunction "1_1") (pintype "passive"))
      (node (ref "U4") (pin "32") (pinfunction "PD2_32") (pintype "bidirectional"))
    )
    (net (code "11") (name "/KEYPAD_ROW1") (class "Default")
      (node (ref "P1") (pin "5") (pinfunction "5_5") (pintype "passive"))
      (node (ref "U4") (pin "14") (pinfunction "PB2_14") (pintype "bidirectional"))
    )
    (net (code "12") (name "/KEYPAD_ROW2") (class "Default")
      (node (ref "P1") (pin "6") (pinfunction "6_6") (pintype "passive"))
      (node (ref "P4") (pin "1") (pinfunction "1_1") (pintype "passive"))
    )
    (net (code "13") (name "/KEYPAD_ROW3") (class "Default")
      (node (ref "P1") (pin "7") (pinfunction "7_7") (pintype "passive"))
      (node (ref "P3") (pin "1") (pinfunction "1_1") (pintype "passive"))
    )
    (net (code "14") (name "/KEYPAD_ROW4") (class "Default")
      (node (ref "P1") (pin "8") (pinfunction "8_8") (pintype "passive"))
      (node (ref "P2") (pin "1") (pinfunction "1_1") (pintype "passive"))
    )
    (net (code "15") (name "/MISO") (class "Default")
      (node (ref "Conn") (pin "2") (pinfunction "2_2") (pintype "passive"))
      (node (ref "P3") (pin "2") (pinfunction "2_2") (pintype "passive"))
      (node (ref "U4") (pin "16") (pinfunction "PB4_16") (pintype "bidirectional"))
    )
    (net (code "16") (name "/MOSI") (class "Default")
      (node (ref "Conn") (pin "3") (pinfunction "3_3") (pintype "passive"))
      (node (ref "P4") (pin "2") (pinfunction "2_2") (pintype "passive"))
      (node (ref "U4") (pin "15") (pinfunction "PB3_15") (pintype "bidirectional"))
    )
    (net (code "17") (name "/NET_PIN") (class "Default")
      (node (ref "M1") (pin "41") (pinfunction "NETLIGHT_41") (pintype "passive"))
      (node (ref "R9") (pin "2") (pinfunction "2_2") (pintype "passive"))
    )
    (net (code "18") (name "/PWRKEY") (class "Default")
      (node (ref "M1") (pin "39") (pinfunction "POWERKEY_39") (pintype "passive"))
      (node (ref "Q4") (pin "3") (pinfunction "C_3") (pintype "passive"))
      (node (ref "R4") (pin "2") (pinfunction "2_2") (pintype "passive"))
    )
    (net (code "19") (name "/RELAY1") (class "Default")
      (node (ref "R30") (pin "2") (pinfunction "2_2") (pintype "passive"))
      (node (ref "R33") (pin "2") (pinfunction "2_2") (pintype "passive"))
      (node (ref "U4") (pin "23") (pinfunction "PC0_23") (pintype "bidirectional"))
    )
    (net (code "20") (name "/RELAY2") (class "Default")
      (node (ref "R31") (pin "2") (pinfunction "2_2") (pintype "passive"))
      (node (ref "R34") (pin "2") (pinfunction "2_2") (pintype "passive"))
      (node (ref "U4") (pin "24") (pinfunction "PC1_24") (pintype "bidirectional"))
    )
    (net (code "21") (name "/RELAY3") (class "Default")
      (node (ref "R32") (pin "2") (pinfunction "2_2") (pintype "passive"))
      (node (ref "R35") (pin "2") (pinfunction "2_2") (pintype "passive"))
      (node (ref "U4") (pin "25") (pinfunction "PC2_25") (pintype "bidirectional"))
    )
    (net (code "22") (name "/RESET") (class "Default")
      (node (ref "C27") (pin "1") (pinfunction "1_1") (pintype "passive"))
      (node (ref "Conn") (pin "5") (pinfunction "5_5") (pintype "passive"))
      (node (ref "D7") (pin "2") (pinfunction "2_2") (pintype "passive"))
      (node (ref "R26") (pin "1") (pinfunction "1_1") (pintype "passive"))
      (node (ref "S4") (pin "2") (pinfunction "2_2") (pintype "passive"))
      (node (ref "U4") (pin "29") (pinfunction "PC6/!RESET_29") (pintype "bidirectional"))
    )
    (net (code "23") (name "/RI_PIN") (class "Default")
      (node (ref "M1") (pin "7") (pinfunction "UART1_RI_7") (pintype "passive"))
      (node (ref "R11") (pin "2") (pinfunction "2_2") (pintype "passive"))
    )
    (net (code "24") (name "/SCK") (class "Default")
      (node (ref "Conn") (pin "1") (pinfunction "1_1") (pintype "passive"))
      (node (ref "P2") (pin "2") (pinfunction "2_2") (pintype "passive"))
      (node (ref "U4") (pin "17") (pinfunction "PB5_17") (pintype "bidirectional"))
    )
    (net (code "25") (name "/SCL") (class "Default")
      (node (ref "L2") (pin "3") (pinfunction "SCL_3") (pintype "passive"))
      (node (ref "R23") (pin "1") (pinfunction "1_1") (pintype "passive"))
      (node (ref "U2") (pin "6") (pinfunction "SCL_6") (pintype "bidirectional"))
      (node (ref "U3") (pin "6") (pinfunction "SCL_6") (pintype "passive"))
      (node (ref "U4") (pin "28") (pinfunction "PC5_28") (pintype "bidirectional"))
    )
    (net (code "26") (name "/SDA") (class "Default")
      (node (ref "L2") (pin "4") (pinfunction "SDA_4") (pintype "passive"))
      (node (ref "R22") (pin "1") (pinfunction "1_1") (pintype "passive"))
      (node (ref "U2") (pin "5") (pinfunction "SDA_5") (pintype "bidirectional"))
      (node (ref "U3") (pin "5") (pinfunction "SDA_5") (pintype "power_in"))
      (node (ref "U4") (pin "27") (pinfunction "PC4_27") (pintype "bidirectional"))
    )
    (net (code "27") (name "/SENSOR_DATA") (class "Default")
      (node (ref "DHT22") (pin "2") (pinfunction "DATA_2") (pintype "passive"))
      (node (ref "R21") (pin "1") (pinfunction "1_1") (pintype "passive"))
      (node (ref "U4") (pin "9") (pinfunction "PD5_9") (pintype "bidirectional"))
    )
    (net (code "28") (name "/SIM800_VRTC") (class "Default")
      (node (ref "C26") (pin "1") (pintype "passive"))
      (node (ref "M1") (pin "28") (pinfunction "VRTC_28") (pintype "passive"))
    )
    (net (code "29") (name "/SIM_CLK") (class "Default")
      (node (ref "C18") (pin "1") (pinfunction "1_1") (pintype "passive"))
      (node (ref "M1") (pin "16") (pinfunction "SIM_CLK_16") (pintype "passive"))
      (node (ref "R19") (pin "1") (pinfunction "1_1") (pintype "passive"))
    )
    (net (code "30") (name "/SIM_DATA") (class "Default")
      (node (ref "C15") (pin "2") (pinfunction "2_2") (pintype "passive"))
      (node (ref "M1") (pin "15") (pinfunction "SIM_DATA_15") (pintype "passive"))
      (node (ref "R18") (pin "1") (pinfunction "1_1") (pintype "passive"))
    )
    (net (code "31") (name "/SIM_RESET") (class "Default")
      (node (ref "R10") (pin "2") (pinfunction "2_2") (pintype "passive"))
      (node (ref "U4") (pin "2") (pinfunction "PD4_2") (pintype "bidirectional"))
    )
    (net (code "32") (name "/SIM_RST") (class "Default")
      (node (ref "C17") (pin "1") (pinfunction "1_1") (pintype "passive"))
      (node (ref "M1") (pin "17") (pinfunction "SIM_RST_17") (pintype "passive"))
      (node (ref "R20") (pin "1") (pinfunction "1_1") (pintype "passive"))
    )
    (net (code "33") (name "/SIM_RXD") (class "Default")
      (node (ref "U4") (pin "31") (pinfunction "PD1_31") (pintype "bidirectional"))
    )
    (net (code "34") (name "/SIM_STATUS") (class "Default")
      (node (ref "M1") (pin "42") (pinfunction "STATUS_42") (pintype "passive"))
      (node (ref "R8") (pin "2") (pinfunction "2_2") (pintype "passive"))
      (node (ref "U4") (pin "1") (pinfunction "PD3_1") (pintype "bidirectional"))
    )
    (net (code "35") (name "/SIM_TXD") (class "Default")
      (node (ref "U4") (pin "30") (pinfunction "PD0_30") (pintype "bidirectional"))
    )
    (net (code "36") (name "/SIM_VDD") (class "Default")
      (node (ref "C19") (pin "2") (pinfunction "2_2") (pintype "passive"))
      (node (ref "J3") (pin "1") (pinfunction "VCC_1") (pintype "passive"))
      (node (ref "M1") (pin "18") (pinfunction "SIM_VDD_18") (pintype "passive"))
    )
    (net (code "37") (name "/Sim800_RX") (class "Default")
      (node (ref "R24") (pin "2") (pinfunction "2_2") (pintype "passive"))
    )
    (net (code "38") (name "/Sim800_TX") (class "Default")
      (node (ref "M1") (pin "1") (pinfunction "UART1_TXD_1") (pintype "output"))
    )
    (net (code "39") (name "COM2") (class "Default")
      (node (ref "*7") (pin "3") (pinfunction "3_3") (pintype "passive"))
      (node (ref "X2") (pin "2") (pinfunction "2_2") (pintype "passive"))
    )
    (net (code "40") (name "COM3") (class "Default")
      (node (ref "*8") (pin "3") (pinfunction "3_3") (pintype "passive"))
      (node (ref "X3") (pin "2") (pinfunction "2_2") (pintype "passive"))
    )
    (net (code "41") (name "GND") (class "Default")
      (node (ref "*1") (pin "2") (pinfunction "-_2") (pintype "passive"))
      (node (ref "C1") (pin "2") (pintype "passive"))
      (node (ref "C10") (pin "1") (pinfunction "1_1") (pintype "passive"))
      (node (ref "C11") (pin "2") (pintype "passive"))
      (node (ref "C12") (pin "1") (pinfunction "1_1") (pintype "passive"))
      (node (ref "C13") (pin "1") (pinfunction "1_1") (pintype "passive"))
      (node (ref "C14") (pin "1") (pinfunction "1_1") (pintype "passive"))
      (node (ref "C15") (pin "1") (pinfunction "1_1") (pintype "passive"))
      (node (ref "C16") (pin "2") (pinfunction "2_2") (pintype "passive"))
      (node (ref "C17") (pin "2") (pinfunction "2_2") (pintype "passive"))
      (node (ref "C18") (pin "2") (pinfunction "2_2") (pintype "passive"))
      (node (ref "C19") (pin "1") (pinfunction "1_1") (pintype "passive"))
      (node (ref "C2") (pin "2") (pinfunction "2_2") (pintype "passive"))
      (node (ref "C20") (pin "1") (pinfunction "1_1") (pintype "passive"))
      (node (ref "C21") (pin "1") (pinfunction "1_1") (pintype "passive"))
      (node (ref "C22") (pin "1") (pinfunction "1_1") (pintype "passive"))
      (node (ref "C23") (pin "1") (pinfunction "1_1") (pintype "passive"))
      (node (ref "C24") (pin "1") (pinfunction "1_1") (pintype "passive"))
      (node (ref "C25") (pin "1") (pinfunction "1_1") (pintype "passive"))
      (node (ref "C26") (pin "2") (pintype "passive"))
      (node (ref "C27") (pin "2") (pinfunction "2_2") (pintype "passive"))
      (node (ref "C3") (pin "2") (pinfunction "2_2") (pintype "passive"))
      (node (ref "C4") (pin "1") (pinfunction "1_1") (pintype "passive"))
      (node (ref "C5") (pin "1") (pinfunction "1_1") (pintype "passive"))
      (node (ref "C6") (pin "1") (pinfunction "1_1") (pintype "passive"))
      (node (ref "C7") (pin "1") (pinfunction "1_1") (pintype "passive"))
      (node (ref "C8") (pin "1") (pinfunction "1_1") (pintype "passive"))
      (node (ref "C9") (pin "1") (pinfunction "1_1") (pintype "passive"))
      (node (ref "Conn") (pin "4") (pinfunction "4_4") (pintype "passive"))
      (node (ref "D3") (pin "1") (pinfunction "A_1") (pintype "passive"))
      (node (ref "D5") (pin "2") (pinfunction "2_2") (pintype "passive"))
      (node (ref "D6") (pin "1") (pinfunction "1_1") (pintype "passive"))
      (node (ref "DHT22") (pin "4") (pinfunction "GND_4") (pintype "passive"))
      (node (ref "J2") (pin "2") (pinfunction "2_2") (pintype "power_in"))
      (node (ref "J2") (pin "3") (pinfunction "3_3") (pintype "power_in"))
      (node (ref "J3") (pin "4") (pinfunction "GND_4") (pintype "passive"))
      (node (ref "J3") (pin "Z1") (pinfunction "Shield_Z1") (pintype "passive"))
      (node (ref "J3") (pin "Z2") (pinfunction "Shield_Z2") (pintype "passive"))
      (node (ref "L2") (pin "1") (pinfunction "GND_1") (pintype "passive"))
      (node (ref "M1") (pin "13") (pinfunction "GND_13") (pintype "passive"))
      (node (ref "M1") (pin "19") (pinfunction "GND_19") (pintype "passive"))
      (node (ref "M1") (pin "21") (pinfunction "GND_21") (pintype "passive"))
      (node (ref "M1") (pin "27") (pinfunction "GND_27") (pintype "passive"))
      (node (ref "M1") (pin "30") (pinfunction "GND_30") (pintype "passive"))
      (node (ref "M1") (pin "31") (pinfunction "GND_31") (pintype "passive"))
      (node (ref "M1") (pin "33") (pinfunction "GND_33") (pintype "passive"))
      (node (ref "M1") (pin "36") (pinfunction "GND_36") (pintype "passive"))
      (node (ref "M1") (pin "37") (pinfunction "GND_37") (pintype "passive"))
      (node (ref "M1") (pin "8") (pinfunction "GND_8") (pintype "passive"))
      (node (ref "Q1") (pin "2") (pinfunction "E_2") (pintype "passive"))
      (node (ref "Q10") (pin "2") (pinfunction "E_2") (pintype "passive"))
      (node (ref "Q11") (pin "2") (pinfunction "E_2") (pintype "passive"))
      (node (ref "Q2") (pin "2") (pinfunction "E_2") (pintype "passive"))
      (node (ref "Q3") (pin "2") (pinfunction "E_2") (pintype "passive"))
      (node (ref "Q4") (pin "2") (pinfunction "E_2") (pintype "passive"))
      (node (ref "Q5") (pin "2") (pinfunction "E_2") (pintype "passive"))
      (node (ref "Q6") (pin "2") (pinfunction "E_2") (pintype "passive"))
      (node (ref "Q7") (pin "2") (pinfunction "E_2") (pintype "passive"))
      (node (ref "Q8") (pin "2") (pinfunction "E_2") (pintype "passive"))
      (node (ref "Q9") (pin "2") (pinfunction "E_2") (pintype "passive"))
      (node (ref "R12") (pin "1") (pinfunction "1_1") (pintype "passive"))
      (node (ref "R13") (pin "1") (pinfunction "1_1") (pintype "passive"))
      (node (ref "R14") (pin "1") (pinfunction "1_1") (pintype "passive"))
      (node (ref "R15") (pin "1") (pinfunction "1_1") (pintype "passive"))
      (node (ref "R16") (pin "1") (pinfunction "1_1") (pintype "passive"))
      (node (ref "R25") (pin "2") (pinfunction "2_2") (pintype "passive"))
      (node (ref "R36") (pin "1") (pinfunction "1_1") (pintype "passive"))
      (node (ref "R37") (pin "1") (pinfunction "1_1") (pintype "passive"))
      (node (ref "R38") (pin "1") (pinfunction "1_1") (pintype "passive"))
      (node (ref "R39") (pin "1") (pinfunction "1_1") (pintype "passive"))
      (node (ref "R40") (pin "1") (pinfunction "1_1") (pintype "passive"))
      (node (ref "R41") (pin "1") (pinfunction "1_1") (pintype "passive"))
      (node (ref "Reg1") (pin "1") (pinfunction "GND_1") (pintype "passive"))
      (node (ref "S1") (pin "1") (pinfunction "Button_1") (pintype "passive"))
      (node (ref "S4") (pin "1") (pinfunction "Button_1") (pintype "passive"))
      (node (ref "SMA1") (pin "2") (pinfunction "GND_2") (pintype "power_in"))
      (node (ref "SMA1") (pin "3") (pinfunction "GND_3") (pintype "power_in"))
      (node (ref "SMA1") (pin "4") (pinfunction "GND_4") (pintype "power_in"))
      (node (ref "SMA1") (pin "5") (pinfunction "GND_5") (pintype "power_in"))
      (node (ref "SMA2") (pin "2") (pinfunction "GND_2") (pintype "power_in"))
      (node (ref "SMA2") (pin "3") (pinfunction "GND_3") (pintype "power_in"))
      (node (ref "SMA2") (pin "4") (pinfunction "GND_4") (pintype "power_in"))
      (node (ref "SMA2") (pin "5") (pinfunction "GND_5") (pintype "power_in"))
      (node (ref "U1") (pin "3") (pinfunction "GND_3") (pintype "power_in"))
      (node (ref "U1") (pin "5") (pinfunction "~{ON}/OFF_5") (pintype "input"))
      (node (ref "U2") (pin "4") (pinfunction "GND_4") (pintype "power_in"))
      (node (ref "U3") (pin "1") (pinfunction "A0_1") (pintype "input"))
      (node (ref "U3") (pin "2") (pinfunction "A1_2") (pintype "input"))
      (node (ref "U3") (pin "3") (pinfunction "A2_3") (pintype "input"))
      (node (ref "U3") (pin "4") (pinfunction "GND_4") (pintype "power_in"))
      (node (ref "U4") (pin "21") (pinfunction "GND_21") (pintype "power_in"))
      (node (ref "U4") (pin "3") (pinfunction "GND_3") (pintype "power_in"))
      (node (ref "U4") (pin "5") (pinfunction "GND_5") (pintype "power_in"))
      (node (ref "X1") (pin "2") (pinfunction "2_2") (pintype "passive"))
    )
    (net (code "42") (name "NC1") (class "Default")
      (node (ref "*2") (pin "4") (pinfunction "4_4") (pintype "passive"))
      (node (ref "X1") (pin "3") (pinfunction "3_3") (pintype "passive"))
    )
    (net (code "43") (name "NC2") (class "Default")
      (node (ref "*7") (pin "4") (pinfunction "4_4") (pintype "passive"))
      (node (ref "X2") (pin "3") (pinfunction "3_3") (pintype "passive"))
    )
    (net (code "44") (name "NC3") (class "Default")
      (node (ref "*8") (pin "4") (pinfunction "4_4") (pintype "passive"))
      (node (ref "X3") (pin "3") (pinfunction "3_3") (pintype "passive"))
    )
    (net (code "45") (name "NO1") (class "Default")
      (node (ref "*2") (pin "5") (pinfunction "5_5") (pintype "passive"))
      (node (ref "X1") (pin "1") (pinfunction "1_1") (pintype "passive"))
    )
    (net (code "46") (name "NO2") (class "Default")
      (node (ref "*7") (pin "5") (pinfunction "5_5") (pintype "passive"))
      (node (ref "X2") (pin "1") (pinfunction "1_1") (pintype "passive"))
    )
    (net (code "47") (name "NO3") (class "Default")
      (node (ref "*8") (pin "5") (pinfunction "5_5") (pintype "passive"))
      (node (ref "X3") (pin "1") (pinfunction "1_1") (pintype "passive"))
    )
    (net (code "48") (name "Net-(*1-+)") (class "Default")
      (node (ref "*1") (pin "1") (pinfunction "+_1") (pintype "passive"))
      (node (ref "U2") (pin "3") (pinfunction "VBAT_3") (pintype "power_in"))
    )
    (net (code "49") (name "Net-(*3-K)") (class "Default")
      (node (ref "*3") (pin "2") (pinfunction "K_2") (pintype "passive"))
      (node (ref "R27") (pin "2") (pinfunction "2_2") (pintype "passive"))
    )
    (net (code "50") (name "Net-(*4-A)") (class "Default")
      (node (ref "*2") (pin "2") (pinfunction "2_2") (pintype "passive"))
      (node (ref "*4") (pin "1") (pinfunction "A_1") (pintype "passive"))
      (node (ref "Q9") (pin "3") (pinfunction "C_3") (pintype "passive"))
    )
    (net (code "51") (name "Net-(*5-K)") (class "Default")
      (node (ref "*5") (pin "2") (pinfunction "K_2") (pintype "passive"))
      (node (ref "R28") (pin "2") (pinfunction "2_2") (pintype "passive"))
    )
    (net (code "52") (name "Net-(*6-K)") (class "Default")
      (node (ref "*6") (pin "2") (pinfunction "K_2") (pintype "passive"))
      (node (ref "R29") (pin "2") (pinfunction "2_2") (pintype "passive"))
    )
    (net (code "53") (name "Net-(*9-A)") (class "Default")
      (node (ref "*7") (pin "2") (pinfunction "2_2") (pintype "passive"))
      (node (ref "*9") (pin "1") (pinfunction "A_1") (pintype "passive"))
      (node (ref "Q10") (pin "3") (pinfunction "C_3") (pintype "passive"))
    )
    (net (code "54") (name "Net-(*10-A)") (class "Default")
      (node (ref "*10") (pin "1") (pinfunction "A_1") (pintype "passive"))
      (node (ref "*8") (pin "2") (pinfunction "2_2") (pintype "passive"))
      (node (ref "Q11") (pin "3") (pinfunction "C_3") (pintype "passive"))
    )
    (net (code "55") (name "Net-(D1-Pad1)") (class "Default")
      (node (ref "D1") (pin "1") (pinfunction "1_1") (pintype "passive"))
      (node (ref "R3") (pin "2") (pinfunction "2_2") (pintype "passive"))
    )
    (net (code "56") (name "Net-(D2-Pad1)") (class "Default")
      (node (ref "D2") (pin "1") (pinfunction "1_1") (pintype "passive"))
      (node (ref "R2") (pin "2") (pinfunction "2_2") (pintype "passive"))
    )
    (net (code "57") (name "Net-(D3-K)") (class "Default")
      (node (ref "D3") (pin "2") (pinfunction "K_2") (pintype "passive"))
      (node (ref "L1") (pin "1") (pinfunction "1_1") (pintype "passive"))
      (node (ref "U1") (pin "2") (pinfunction "OUT_2") (pintype "power_in"))
    )
    (net (code "58") (name "Net-(D4-Pad2)") (class "Default")
      (node (ref "D4") (pin "2") (pinfunction "2_2") (pintype "passive"))
      (node (ref "R1") (pin "1") (pinfunction "1_1") (pintype "passive"))
    )
    (net (code "59") (name "Net-(D6-Pad2)") (class "Default")
      (node (ref "D6") (pin "2") (pinfunction "2_2") (pintype "passive"))
      (node (ref "R7") (pin "1") (pinfunction "1_1") (pintype "passive"))
    )
    (net (code "60") (name "Net-(J1-Pad1)") (class "Default")
      (node (ref "J1") (pin "1") (pinfunction "1_1") (pintype "passive"))
      (node (ref "J2") (pin "1") (pinfunction "1_1") (pintype "power_in"))
    )
    (net (code "61") (name "Net-(J3-1{slash}0)") (class "Default")
      (node (ref "J3") (pin "6") (pinfunction "1/0_6") (pintype "passive"))
      (node (ref "R18") (pin "2") (pinfunction "2_2") (pintype "passive"))
    )
    (net (code "62") (name "Net-(J3-CLOCK)") (class "Default")
      (node (ref "J3") (pin "3") (pinfunction "CLOCK_3") (pintype "passive"))
      (node (ref "R19") (pin "2") (pinfunction "2_2") (pintype "passive"))
    )
    (net (code "63") (name "Net-(J3-RESET)") (class "Default")
      (node (ref "J3") (pin "2") (pinfunction "RESET_2") (pintype "passive"))
      (node (ref "R20") (pin "2") (pinfunction "2_2") (pintype "passive"))
    )
    (net (code "64") (name "Net-(M1-BT_ANT)") (class "Default")
      (node (ref "M1") (pin "20") (pinfunction "BT_ANT_20") (pintype "passive"))
      (node (ref "SMA2") (pin "1") (pinfunction "Signal_1") (pintype "input"))
    )
    (net (code "65") (name "Net-(M1-UART1_RXD)") (class "Default")
      (node (ref "M1") (pin "2") (pinfunction "UART1_RXD_2") (pintype "input"))
      (node (ref "R24") (pin "1") (pinfunction "1_1") (pintype "passive"))
      (node (ref "R25") (pin "1") (pinfunction "1_1") (pintype "passive"))
    )
    (net (code "66") (name "Net-(Q1-B)") (class "Default")
      (node (ref "Q1") (pin "1") (pinfunction "B_1") (pintype "passive"))
      (node (ref "Q5") (pin "3") (pinfunction "C_3") (pintype "passive"))
      (node (ref "R5") (pin "1") (pinfunction "1_1") (pintype "passive"))
    )
    (net (code "67") (name "Net-(Q1-C)") (class "Default")
      (node (ref "D4") (pin "1") (pinfunction "1_1") (pintype "passive"))
      (node (ref "Q1") (pin "3") (pinfunction "C_3") (pintype "passive"))
    )
    (net (code "68") (name "Net-(Q2-B)") (class "Default")
      (node (ref "Q2") (pin "1") (pinfunction "B_1") (pintype "passive"))
      (node (ref "R13") (pin "2") (pinfunction "2_2") (pintype "passive"))
      (node (ref "R8") (pin "1") (pinfunction "1_1") (pintype "passive"))
    )
    (net (code "69") (name "Net-(Q2-C)") (class "Default")
      (node (ref "Q2") (pin "3") (pinfunction "C_3") (pintype "passive"))
      (node (ref "R3") (pin "1") (pinfunction "1_1") (pintype "passive"))
    )
    (net (code "70") (name "Net-(Q3-B)") (class "Default")
      (node (ref "Q3") (pin "1") (pinfunction "B_1") (pintype "passive"))
      (node (ref "R14") (pin "2") (pinfunction "2_2") (pintype "passive"))
      (node (ref "R9") (pin "1") (pinfunction "1_1") (pintype "passive"))
    )
    (net (code "71") (name "Net-(Q3-C)") (class "Default")
      (node (ref "Q3") (pin "3") (pinfunction "C_3") (pintype "passive"))
      (node (ref "R2") (pin "1") (pinfunction "1_1") (pintype "passive"))
    )
    (net (code "72") (name "Net-(Q4-B)") (class "Default")
      (node (ref "Q4") (pin "1") (pinfunction "B_1") (pintype "passive"))
      (node (ref "R10") (pin "1") (pinfunction "1_1") (pintype "passive"))
      (node (ref "R15") (pin "2") (pinfunction "2_2") (pintype "passive"))
    )
    (net (code "73") (name "Net-(Q5-B)") (class "Default")
      (node (ref "Q5") (pin "1") (pinfunction "B_1") (pintype "passive"))
      (node (ref "R11") (pin "1") (pinfunction "1_1") (pintype "passive"))
      (node (ref "R16") (pin "2") (pinfunction "2_2") (pintype "passive"))
    )
    (net (code "74") (name "Net-(Q6-B)") (class "Default")
      (node (ref "Q6") (pin "1") (pinfunction "B_1") (pintype "passive"))
      (node (ref "R30") (pin "1") (pinfunction "1_1") (pintype "passive"))
      (node (ref "R36") (pin "2") (pinfunction "2_2") (pintype "passive"))
    )
    (net (code "75") (name "Net-(Q6-C)") (class "Default")
      (node (ref "Q6") (pin "3") (pinfunction "C_3") (pintype "passive"))
      (node (ref "R27") (pin "1") (pinfunction "1_1") (pintype "passive"))
    )
    (net (code "76") (name "Net-(Q7-B)") (class "Default")
      (node (ref "Q7") (pin "1") (pinfunction "B_1") (pintype "passive"))
      (node (ref "R31") (pin "1") (pinfunction "1_1") (pintype "passive"))
      (node (ref "R37") (pin "2") (pinfunction "2_2") (pintype "passive"))
    )
    (net (code "77") (name "Net-(Q7-C)") (class "Default")
      (node (ref "Q7") (pin "3") (pinfunction "C_3") (pintype "passive"))
      (node (ref "R28") (pin "1") (pinfunction "1_1") (pintype "passive"))
    )
    (net (code "78") (name "Net-(Q8-B)") (class "Default")
      (node (ref "Q8") (pin "1") (pinfunction "B_1") (pintype "passive"))
      (node (ref "R32") (pin "1") (pinfunction "1_1") (pintype "passive"))
      (node (ref "R38") (pin "2") (pinfunction "2_2") (pintype "passive"))
    )
    (net (code "79") (name "Net-(Q8-C)") (class "Default")
      (node (ref "Q8") (pin "3") (pinfunction "C_3") (pintype "passive"))
      (node (ref "R29") (pin "1") (pinfunction "1_1") (pintype "passive"))
    )
    (net (code "80") (name "Net-(Q9-B)") (class "Default")
      (node (ref "Q9") (pin "1") (pinfunction "B_1") (pintype "passive"))
      (node (ref "R33") (pin "1") (pinfunction "1_1") (pintype "passive"))
      (node (ref "R39") (pin "2") (pinfunction "2_2") (pintype "passive"))
    )
    (net (code "81") (name "Net-(Q10-B)") (class "Default")
      (node (ref "Q10") (pin "1") (pinfunction "B_1") (pintype "passive"))
      (node (ref "R34") (pin "1") (pinfunction "1_1") (pintype "passive"))
      (node (ref "R40") (pin "2") (pinfunction "2_2") (pintype "passive"))
    )
    (net (code "82") (name "Net-(Q11-B)") (class "Default")
      (node (ref "Q11") (pin "1") (pinfunction "B_1") (pintype "passive"))
      (node (ref "R35") (pin "1") (pinfunction "1_1") (pintype "passive"))
      (node (ref "R41") (pin "2") (pinfunction "2_2") (pintype "passive"))
    )
    (net (code "83") (name "Net-(R4-Pad1)") (class "Default")
      (node (ref "R4") (pin "1") (pinfunction "1_1") (pintype "passive"))
      (node (ref "S1") (pin "2") (pinfunction "2_2") (pintype "passive"))
    )
    (net (code "84") (name "Net-(U1-FB)") (class "Default")
      (node (ref "R12") (pin "2") (pinfunction "2_2") (pintype "passive"))
      (node (ref "R6") (pin "1") (pinfunction "1_1") (pintype "passive"))
      (node (ref "U1") (pin "4") (pinfunction "FB_4") (pintype "input"))
    )
    (net (code "85") (name "Net-(U2-X1)") (class "Default")
      (node (ref "Crystal1") (pin "2") (pinfunction "2_2") (pintype "passive"))
      (node (ref "U2") (pin "1") (pinfunction "X1_1") (pintype "bidirectional"))
    )
    (net (code "86") (name "Net-(U2-X2)") (class "Default")
      (node (ref "Crystal1") (pin "1") (pinfunction "1_1") (pintype "passive"))
      (node (ref "U2") (pin "2") (pinfunction "X2_2") (pintype "bidirectional"))
    )
    (net (code "87") (name "Net-(U4-AREF)") (class "Default")
      (node (ref "C20") (pin "2") (pinfunction "2_2") (pintype "passive"))
      (node (ref "U4") (pin "20") (pinfunction "AREF_20") (pintype "input"))
    )
    (net (code "88") (name "Net-(U4-PB6)") (class "Default")
      (node (ref "C24") (pin "2") (pinfunction "2_2") (pintype "passive"))
      (node (ref "U4") (pin "7") (pinfunction "PB6_7") (pintype "bidirectional"))
      (node (ref "Y1") (pin "2") (pinfunction "2_2") (pintype "passive"))
    )
    (net (code "89") (name "Net-(U4-PB7)") (class "Default")
      (node (ref "C25") (pin "2") (pinfunction "2_2") (pintype "passive"))
      (node (ref "U4") (pin "8") (pinfunction "PB7_8") (pintype "bidirectional"))
      (node (ref "Y1") (pin "1") (pinfunction "1_1") (pintype "passive"))
    )
    (net (code "90") (name "unconnected-(DHT22-NC-Pad3)") (class "Default")
      (node (ref "DHT22") (pin "3") (pinfunction "NC_3") (pintype "passive"))
    )
    (net (code "91") (name "unconnected-(J3-VPP-Pad5)") (class "Default")
      (node (ref "J3") (pin "5") (pinfunction "VPP_5") (pintype "passive"))
    )
    (net (code "92") (name "unconnected-(M1-ADC-Pad38)") (class "Default")
      (node (ref "M1") (pin "38") (pinfunction "ADC_38") (pintype "passive"))
    )
    (net (code "93") (name "unconnected-(M1-MIC1N-Pad10)") (class "Default")
      (node (ref "M1") (pin "10") (pinfunction "MIC1N_10") (pintype "passive"))
    )
    (net (code "94") (name "unconnected-(M1-MIC1P-Pad9)") (class "Default")
      (node (ref "M1") (pin "9") (pinfunction "MIC1P_9") (pintype "passive"))
    )
    (net (code "95") (name "unconnected-(M1-RF_SYNC-Pad29)") (class "Default")
      (node (ref "M1") (pin "29") (pinfunction "RF_SYNC_29") (pintype "passive"))
    )
    (net (code "96") (name "unconnected-(M1-SIM_DET-Pad14)") (class "Default")
      (node (ref "M1") (pin "14") (pinfunction "SIM_DET_14") (pintype "passive"))
    )
    (net (code "97") (name "unconnected-(M1-SPK1N-Pad12)") (class "Default")
      (node (ref "M1") (pin "12") (pinfunction "SPK1N_12") (pintype "passive"))
    )
    (net (code "98") (name "unconnected-(M1-SPK1P-Pad11)") (class "Default")
      (node (ref "M1") (pin "11") (pinfunction "SPK1P_11") (pintype "passive"))
    )
    (net (code "99") (name "unconnected-(M1-UART1_CTS-Pad4)") (class "Default")
      (node (ref "M1") (pin "4") (pinfunction "UART1_CTS_4") (pintype "output"))
    )
    (net (code "100") (name "unconnected-(M1-UART1_DCD-Pad5)") (class "Default")
      (node (ref "M1") (pin "5") (pinfunction "UART1_DCD_5") (pintype "passive"))
    )
    (net (code "101") (name "unconnected-(M1-UART1_DTR-Pad6)") (class "Default")
      (node (ref "M1") (pin "6") (pinfunction "UART1_DTR_6") (pintype "passive"))
    )
    (net (code "102") (name "unconnected-(M1-UART1_RTS-Pad3)") (class "Default")
      (node (ref "M1") (pin "3") (pinfunction "UART1_RTS_3") (pintype "input+no_connect"))
    )
    (net (code "103") (name "unconnected-(M1-UART2_RXD-Pad23)") (class "Default")
      (node (ref "M1") (pin "23") (pinfunction "UART2_RXD_23") (pintype "passive"))
    )
    (net (code "104") (name "unconnected-(M1-UART2_TXD-Pad22)") (class "Default")
      (node (ref "M1") (pin "22") (pinfunction "UART2_TXD_22") (pintype "passive"))
    )
    (net (code "105") (name "unconnected-(M1-USB_DN-Pad26)") (class "Default")
      (node (ref "M1") (pin "26") (pinfunction "USB_DN_26") (pintype "passive"))
    )
    (net (code "106") (name "unconnected-(M1-USB_DP-Pad25)") (class "Default")
      (node (ref "M1") (pin "25") (pinfunction "USB_DP_25") (pintype "passive"))
    )
    (net (code "107") (name "unconnected-(M1-USB_VBUS-Pad24)") (class "Default")
      (node (ref "M1") (pin "24") (pinfunction "USB_VBUS_24") (pintype "passive"))
    )
    (net (code "108") (name "unconnected-(M1-VEXT-Pad40)") (class "Default")
      (node (ref "M1") (pin "40") (pinfunction "VEXT_40") (pintype "passive"))
    )
    (net (code "109") (name "unconnected-(U1-TAB-Pad6)") (class "Default")
      (node (ref "U1") (pin "6") (pinfunction "TAB_6") (pintype "power_in"))
    )
    (net (code "110") (name "unconnected-(U2-SQW{slash}OUT-Pad7)") (class "Default")
      (node (ref "U2") (pin "7") (pinfunction "SQW/OUT_7") (pintype "output"))
    )
    (net (code "111") (name "unconnected-(U4-ADC6-Pad19)") (class "Default")
      (node (ref "U4") (pin "19") (pinfunction "ADC6_19") (pintype "bidirectional"))
    )
    (net (code "112") (name "unconnected-(U4-ADC7-Pad22)") (class "Default")
      (node (ref "U4") (pin "22") (pinfunction "ADC7_22") (pintype "bidirectional"))
    )
  )
)
